# CE842170260_SHEET4.net
KiCad netlist of a schematic drawn in Altium Designer
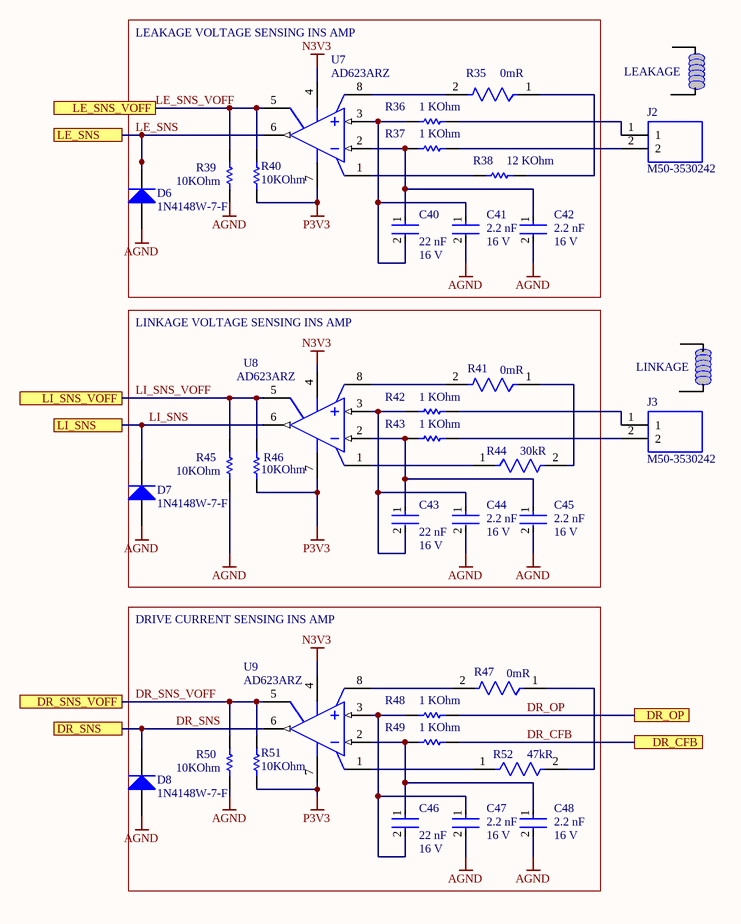
[diagram p0: CE842170260_SHEET4.SchDoc]

(export (version "E")
  (design (tool "Eeschema 10.0.6"))
  (components
    (comp (ref "C40")
      (value "CC0402KRX7R7BB223")
      (footprint "FP-CC0402-MFG")
      (description "CAP CER 0.022UF 16V X7R 0402")
      (fields
        (field (name "VOLTAGE RATING") "16 V")
        (field (name "OCTOPART") "https://octopart.com/cc0402krx7r7bb223-yageo-42244626")
        (field (name "CAPACITANCE") "22 nF")
        (field (name "TOLERANCE") "0.1")
      )
      (libsource (lib "Altium Content Vault") (part "11868f565c42a9108669ba33697ecf6"))
    )
    (comp (ref "C41")
      (value "CC0402KRX7R7BB222")
      (footprint "FP-CC0402-MFG")
      (description "CAP CER 2200PF 16V X7R 0402")
      (fields
        (field (name "OCTOPART") "https://octopart.com/cc0402krx7r7bb222-yageo-12817657")
        (field (name "MANUFACTURER") "YAGEO")
        (field (name "CAPACITANCE") "2.2 nF")
        (field (name "VOLTAGE RATING") "16 V")
      )
      (libsource (lib "Altium Content Vault") (part "11868f565c42a9108669ba33697ecf6"))
    )
    (comp (ref "C42")
      (value "CC0402KRX7R7BB222")
      (footprint "FP-CC0402-MFG")
      (description "CAP CER 2200PF 16V X7R 0402")
      (fields
        (field (name "OCTOPART") "https://octopart.com/cc0402krx7r7bb222-yageo-12817657")
        (field (name "MANUFACTURER") "YAGEO")
        (field (name "CAPACITANCE") "2.2 nF")
        (field (name "VOLTAGE RATING") "16 V")
      )
      (libsource (lib "Altium Content Vault") (part "11868f565c42a9108669ba33697ecf6"))
    )
    (comp (ref "C43")
      (value "CC0402KRX7R7BB223")
      (footprint "FP-CC0402-MFG")
      (description "CAP CER 0.022UF 16V X7R 0402")
      (fields
        (field (name "VOLTAGE RATING") "16 V")
        (field (name "OCTOPART") "https://octopart.com/cc0402krx7r7bb223-yageo-42244626")
        (field (name "CAPACITANCE") "22 nF")
        (field (name "TOLERANCE") "0.1")
      )
      (libsource (lib "Altium Content Vault") (part "11868f565c42a9108669ba33697ecf6"))
    )
    (comp (ref "C44")
      (value "CC0402KRX7R7BB222")
      (footprint "FP-CC0402-MFG")
      (description "CAP CER 2200PF 16V X7R 0402")
      (fields
        (field (name "OCTOPART") "https://octopart.com/cc0402krx7r7bb222-yageo-12817657")
        (field (name "MANUFACTURER") "YAGEO")
        (field (name "CAPACITANCE") "2.2 nF")
        (field (name "VOLTAGE RATING") "16 V")
      )
      (libsource (lib "Altium Content Vault") (part "11868f565c42a9108669ba33697ecf6"))
    )
    (comp (ref "C45")
      (value "CC0402KRX7R7BB222")
      (footprint "FP-CC0402-MFG")
      (description "CAP CER 2200PF 16V X7R 0402")
      (fields
        (field (name "OCTOPART") "https://octopart.com/cc0402krx7r7bb222-yageo-12817657")
        (field (name "MANUFACTURER") "YAGEO")
        (field (name "CAPACITANCE") "2.2 nF")
        (field (name "VOLTAGE RATING") "16 V")
      )
      (libsource (lib "Altium Content Vault") (part "11868f565c42a9108669ba33697ecf6"))
    )
    (comp (ref "C46")
      (value "CC0402KRX7R7BB223")
      (footprint "FP-CC0402-MFG")
      (description "CAP CER 0.022UF 16V X7R 0402")
      (fields
        (field (name "VOLTAGE RATING") "16 V")
        (field (name "OCTOPART") "https://octopart.com/cc0402krx7r7bb223-yageo-42244626")
        (field (name "CAPACITANCE") "22 nF")
        (field (name "TOLERANCE") "0.1")
      )
      (libsource (lib "Altium Content Vault") (part "11868f565c42a9108669ba33697ecf6"))
    )
    (comp (ref "C47")
      (value "CC0402KRX7R7BB222")
      (footprint "FP-CC0402-MFG")
      (description "CAP CER 2200PF 16V X7R 0402")
      (fields
        (field (name "OCTOPART") "https://octopart.com/cc0402krx7r7bb222-yageo-12817657")
        (field (name "MANUFACTURER") "YAGEO")
        (field (name "CAPACITANCE") "2.2 nF")
        (field (name "VOLTAGE RATING") "16 V")
      )
      (libsource (lib "Altium Content Vault") (part "11868f565c42a9108669ba33697ecf6"))
    )
    (comp (ref "C48")
      (value "CC0402KRX7R7BB222")
      (footprint "FP-CC0402-MFG")
      (description "CAP CER 2200PF 16V X7R 0402")
      (fields
        (field (name "OCTOPART") "https://octopart.com/cc0402krx7r7bb222-yageo-12817657")
        (field (name "MANUFACTURER") "YAGEO")
        (field (name "CAPACITANCE") "2.2 nF")
        (field (name "VOLTAGE RATING") "16 V")
      )
      (libsource (lib "Altium Content Vault") (part "11868f565c42a9108669ba33697ecf6"))
    )
    (comp (ref "D6")
      (value "1N4148W-7-F")
      (footprint "DIOD-SOD123-2_V")
      (description "Fast Switching Diode, 100 V, 0.15 A, -65 to 150 degC, 2-Pin?SOD123, RoHS, Tape and Reel")
      (fields (field (name "MANUFACTURER") "DiodesIncorporated"))
      (libsource (lib "Altium Content Vault") (part "D-AK-2"))
    )
    (comp (ref "D7")
      (value "1N4148W-7-F")
      (footprint "DIOD-SOD123-2_V")
      (description "Fast Switching Diode, 100 V, 0.15 A, -65 to 150 degC, 2-Pin?SOD123, RoHS, Tape and Reel")
      (fields (field (name "MANUFACTURER") "DiodesIncorporated"))
      (libsource (lib "Altium Content Vault") (part "D-AK-2"))
    )
    (comp (ref "D8")
      (value "1N4148W-7-F")
      (footprint "DIOD-SOD123-2_V")
      (description "Fast Switching Diode, 100 V, 0.15 A, -65 to 150 degC, 2-Pin?SOD123, RoHS, Tape and Reel")
      (fields (field (name "MANUFACTURER") "DiodesIncorporated"))
      (libsource (lib "Altium Content Vault") (part "D-AK-2"))
    )
    (comp (ref "J2")
      (value "M50-3530242")
      (footprint "HDRV2W40P0X127_1X2_254X210X420P")
      (description "Headers & Wire Housings 2 WAY SIL VERT PC TAIL P/HDR")
      (fields (field (name "MOUSER PART NUMBER") "855-M50-3530242"))
      (libsource (lib "M50-3530242") (part "M50-3530242"))
    )
    (comp (ref "J3")
      (value "M50-3530242")
      (footprint "HDRV2W40P0X127_1X2_254X210X420P")
      (description "Headers & Wire Housings 2 WAY SIL VERT PC TAIL P/HDR")
      (fields (field (name "MOUSER PART NUMBER") "855-M50-3530242"))
      (libsource (lib "M50-3530242") (part "M50-3530242"))
    )
    (comp (ref "R35")
      (value "MCS04020Z0000ZE000")
      (footprint "FP-MCS0402-MFG")
      (description "RES SMD 1.2K OHM 1% 1/10W 0402")
      (fields (field (name "RESISTANCE") "0mR"))
      (libsource (lib "Altium Content Vault") (part "1029c3af85768c4190bb7ad29bc67b5"))
    )
    (comp (ref "R36")
      (value "ERJ-2RKF1001X")
      (footprint "RESC1005X40X25NL05T05")
      (description "Chip Resistor, 1 KOhm, +/- 1%, 100 mW, -55 to 155 degC, 0402 (1005 Metric), RoHS, Tape and Reel")
      (fields
        (field (name "MANUFACTURER") "Basic Passives")
        (field (name "TOLERANCE") "1%")
        (field (name "RESISTANCE") "1 KOhm")
      )
      (libsource (lib "Altium Content Vault") (part "RES-2"))
    )
    (comp (ref "R37")
      (value "ERJ-2RKF1001X")
      (footprint "RESC1005X40X25NL05T05")
      (description "Chip Resistor, 1 KOhm, +/- 1%, 100 mW, -55 to 155 degC, 0402 (1005 Metric), RoHS, Tape and Reel")
      (fields
        (field (name "MANUFACTURER") "Basic Passives")
        (field (name "TOLERANCE") "1%")
        (field (name "RESISTANCE") "1 KOhm")
      )
      (libsource (lib "Altium Content Vault") (part "RES-2"))
    )
    (comp (ref "R38")
      (value "ERJ-2RKF1202X")
      (footprint "RESC1005X40X25ML05T05")
      (description "Chip Resistor, 12 KOhm, +/- 1%, 0.1 W, -55 to 155 degC, 0402 (1005 Metric), RoHS, Tape and Reel")
      (fields (field (name "RESISTANCE") "12 KOhm") (field (name "TOLERANCE") "1%"))
      (libsource (lib "Altium Content Vault") (part "RES-2"))
    )
    (comp (ref "R39")
      (value "ERJ2RKF1002X")
      (footprint "RESC1005X40X25LL05T05")
      (description "Chip Resistor, 10 KOhm, +/- 1%, 0.1 W, -55 to 155 degC, 0402 (1005 Metric), RoHS, Tape and Reel")
      (fields
        (field (name "RESISTANCE") "10KOhm")
        (field (name "TOLERANCE") "1%")
        (field (name "MANUFACTURER") "Panasonic")
      )
      (libsource (lib "Altium Content Vault") (part "RES-2"))
    )
    (comp (ref "R40")
      (value "ERJ2RKF1002X")
      (footprint "RESC1005X40X25LL05T05")
      (description "Chip Resistor, 10 KOhm, +/- 1%, 0.1 W, -55 to 155 degC, 0402 (1005 Metric), RoHS, Tape and Reel")
      (fields
        (field (name "RESISTANCE") "10KOhm")
        (field (name "TOLERANCE") "1%")
        (field (name "MANUFACTURER") "Panasonic")
      )
      (libsource (lib "Altium Content Vault") (part "RES-2"))
    )
    (comp (ref "R41")
      (value "MCS04020Z0000ZE000")
      (footprint "FP-MCS0402-MFG")
      (description "RES SMD 1.2K OHM 1% 1/10W 0402")
      (fields (field (name "RESISTANCE") "0mR"))
      (libsource (lib "Altium Content Vault") (part "1029c3af85768c4190bb7ad29bc67b5"))
    )
    (comp (ref "R42")
      (value "ERJ-2RKF1001X")
      (footprint "RESC1005X40X25NL05T05")
      (description "Chip Resistor, 1 KOhm, +/- 1%, 100 mW, -55 to 155 degC, 0402 (1005 Metric), RoHS, Tape and Reel")
      (fields
        (field (name "MANUFACTURER") "Basic Passives")
        (field (name "TOLERANCE") "1%")
        (field (name "RESISTANCE") "1 KOhm")
      )
      (libsource (lib "Altium Content Vault") (part "RES-2"))
    )
    (comp (ref "R43")
      (value "ERJ-2RKF1001X")
      (footprint "RESC1005X40X25NL05T05")
      (description "Chip Resistor, 1 KOhm, +/- 1%, 100 mW, -55 to 155 degC, 0402 (1005 Metric), RoHS, Tape and Reel")
      (fields
        (field (name "MANUFACTURER") "Basic Passives")
        (field (name "TOLERANCE") "1%")
        (field (name "RESISTANCE") "1 KOhm")
      )
      (libsource (lib "Altium Content Vault") (part "RES-2"))
    )
    (comp (ref "R44")
      (value "ERJ-2RKF3002X")
      (footprint "FP-ERJ2RK-IPC_C")
      (description "RES SMD 30K OHM 1% 1/10W 0402")
      (fields (field (name "RESISTANCE") "30kR") (field (name "TOLERANCE") "1%"))
      (libsource (lib "Altium Content Vault") (part "1029c3af85768c4190bb7ad29bc67b5"))
    )
    (comp (ref "R45")
      (value "ERJ2RKF1002X")
      (footprint "RESC1005X40X25LL05T05")
      (description "Chip Resistor, 10 KOhm, +/- 1%, 0.1 W, -55 to 155 degC, 0402 (1005 Metric), RoHS, Tape and Reel")
      (fields
        (field (name "RESISTANCE") "10KOhm")
        (field (name "TOLERANCE") "1%")
        (field (name "MANUFACTURER") "Panasonic")
      )
      (libsource (lib "Altium Content Vault") (part "RES-2"))
    )
    (comp (ref "R46")
      (value "ERJ2RKF1002X")
      (footprint "RESC1005X40X25LL05T05")
      (description "Chip Resistor, 10 KOhm, +/- 1%, 0.1 W, -55 to 155 degC, 0402 (1005 Metric), RoHS, Tape and Reel")
      (fields
        (field (name "RESISTANCE") "10KOhm")
        (field (name "TOLERANCE") "1%")
        (field (name "MANUFACTURER") "Panasonic")
      )
      (libsource (lib "Altium Content Vault") (part "RES-2"))
    )
    (comp (ref "R47")
      (value "MCS04020Z0000ZE000")
      (footprint "FP-MCS0402-MFG")
      (description "RES SMD 1.2K OHM 1% 1/10W 0402")
      (fields (field (name "RESISTANCE") "0mR"))
      (libsource (lib "Altium Content Vault") (part "1029c3af85768c4190bb7ad29bc67b5"))
    )
    (comp (ref "R48")
      (value "ERJ-2RKF1001X")
      (footprint "RESC1005X40X25NL05T05")
      (description "Chip Resistor, 1 KOhm, +/- 1%, 100 mW, -55 to 155 degC, 0402 (1005 Metric), RoHS, Tape and Reel")
      (fields
        (field (name "MANUFACTURER") "Basic Passives")
        (field (name "TOLERANCE") "1%")
        (field (name "RESISTANCE") "1 KOhm")
      )
      (libsource (lib "Altium Content Vault") (part "RES-2"))
    )
    (comp (ref "R49")
      (value "ERJ-2RKF1001X")
      (footprint "RESC1005X40X25NL05T05")
      (description "Chip Resistor, 1 KOhm, +/- 1%, 100 mW, -55 to 155 degC, 0402 (1005 Metric), RoHS, Tape and Reel")
      (fields
        (field (name "MANUFACTURER") "Basic Passives")
        (field (name "TOLERANCE") "1%")
        (field (name "RESISTANCE") "1 KOhm")
      )
      (libsource (lib "Altium Content Vault") (part "RES-2"))
    )
    (comp (ref "R50")
      (value "ERJ2RKF1002X")
      (footprint "RESC1005X40X25LL05T05")
      (description "Chip Resistor, 10 KOhm, +/- 1%, 0.1 W, -55 to 155 degC, 0402 (1005 Metric), RoHS, Tape and Reel")
      (fields
        (field (name "RESISTANCE") "10KOhm")
        (field (name "TOLERANCE") "1%")
        (field (name "MANUFACTURER") "Panasonic")
      )
      (libsource (lib "Altium Content Vault") (part "RES-2"))
    )
    (comp (ref "R51")
      (value "ERJ2RKF1002X")
      (footprint "RESC1005X40X25LL05T05")
      (description "Chip Resistor, 10 KOhm, +/- 1%, 0.1 W, -55 to 155 degC, 0402 (1005 Metric), RoHS, Tape and Reel")
      (fields
        (field (name "RESISTANCE") "10KOhm")
        (field (name "TOLERANCE") "1%")
        (field (name "MANUFACTURER") "Panasonic")
      )
      (libsource (lib "Altium Content Vault") (part "RES-2"))
    )
    (comp (ref "R52")
      (value "ERJ-2RKF4702X")
      (footprint "FP-ERJ2RK-IPC_B")
      (description "RES SMD 47K OHM 1% 1/10W 0402")
      (fields (field (name "RESISTANCE") "47kR") (field (name "TOLERANCE") "1%"))
      (libsource (lib "Altium Content Vault") (part "1029c3af85768c4190bb7ad29bc67b5"))
    )
    (comp (ref "U7")
      (value "AD623ARZ")
      (footprint "ADI-AD623ARZ-8_M")
      (fields (field (name "MANUFACTURER") "Analog Devices"))
      (libsource (lib "Altium Content Vault") (part "ADI-AD623ARZ-8"))
    )
    (comp (ref "U8")
      (value "AD623ARZ")
      (footprint "ADI-AD623ARZ-8_M")
      (fields (field (name "MANUFACTURER") "Analog Devices"))
      (libsource (lib "Altium Content Vault") (part "ADI-AD623ARZ-8"))
    )
    (comp (ref "U9")
      (value "AD623ARZ")
      (footprint "ADI-AD623ARZ-8_M")
      (fields (field (name "MANUFACTURER") "Analog Devices"))
      (libsource (lib "Altium Content Vault") (part "ADI-AD623ARZ-8"))
    )
  )
  (nets
    (net (code "1") (name "/DR_CFB") (class "Default")
      (node (ref "R49") (pin "1") (pinfunction "1_1") (pintype "passive"))
    )
    (net (code "2") (name "/DR_OP") (class "Default")
      (node (ref "R48") (pin "1") (pinfunction "1_1") (pintype "passive"))
    )
    (net (code "3") (name "/DR_SNS") (class "Default")
      (node (ref "D8") (pin "2") (pinfunction "K_2") (pintype "passive"))
      (node (ref "U9") (pin "6") (pinfunction "OUTPUT_6") (pintype "output"))
    )
    (net (code "4") (name "/DR_SNS_VOFF") (class "Default")
      (node (ref "R50") (pin "2") (pinfunction "2_2") (pintype "passive"))
      (node (ref "R51") (pin "1") (pinfunction "1_1") (pintype "passive"))
      (node (ref "U9") (pin "5") (pinfunction "REF_5") (pintype "power_in"))
    )
    (net (code "5") (name "/LE_SNS") (class "Default")
      (node (ref "D6") (pin "2") (pinfunction "K_2") (pintype "passive"))
      (node (ref "U7") (pin "6") (pinfunction "OUTPUT_6") (pintype "output"))
    )
    (net (code "6") (name "/LE_SNS_VOFF") (class "Default")
      (node (ref "R39") (pin "2") (pinfunction "2_2") (pintype "passive"))
      (node (ref "R40") (pin "1") (pinfunction "1_1") (pintype "passive"))
      (node (ref "U7") (pin "5") (pinfunction "REF_5") (pintype "power_in"))
    )
    (net (code "7") (name "/LI_SNS") (class "Default")
      (node (ref "D7") (pin "2") (pinfunction "K_2") (pintype "passive"))
      (node (ref "U8") (pin "6") (pinfunction "OUTPUT_6") (pintype "output"))
    )
    (net (code "8") (name "/LI_SNS_VOFF") (class "Default")
      (node (ref "R45") (pin "2") (pinfunction "2_2") (pintype "passive"))
      (node (ref "R46") (pin "1") (pinfunction "1_1") (pintype "passive"))
      (node (ref "U8") (pin "5") (pinfunction "REF_5") (pintype "power_in"))
    )
    (net (code "9") (name "AGND") (class "Default")
      (node (ref "C41") (pin "2") (pinfunction "2_2") (pintype "passive"))
      (node (ref "C42") (pin "2") (pinfunction "2_2") (pintype "passive"))
      (node (ref "C44") (pin "2") (pinfunction "2_2") (pintype "passive"))
      (node (ref "C45") (pin "2") (pinfunction "2_2") (pintype "passive"))
      (node (ref "C47") (pin "2") (pinfunction "2_2") (pintype "passive"))
      (node (ref "C48") (pin "2") (pinfunction "2_2") (pintype "passive"))
      (node (ref "D6") (pin "1") (pinfunction "A_1") (pintype "passive"))
      (node (ref "D7") (pin "1") (pinfunction "A_1") (pintype "passive"))
      (node (ref "D8") (pin "1") (pinfunction "A_1") (pintype "passive"))
      (node (ref "R39") (pin "1") (pinfunction "1_1") (pintype "passive"))
      (node (ref "R45") (pin "1") (pinfunction "1_1") (pintype "passive"))
      (node (ref "R50") (pin "1") (pinfunction "1_1") (pintype "passive"))
    )
    (net (code "10") (name "N3V3") (class "Default")
      (node (ref "U7") (pin "4") (pinfunction "-VS_4") (pintype "power_in"))
      (node (ref "U8") (pin "4") (pinfunction "-VS_4") (pintype "power_in"))
      (node (ref "U9") (pin "4") (pinfunction "-VS_4") (pintype "power_in"))
    )
    (net (code "11") (name "Net-(J2-Pad1)") (class "Default")
      (node (ref "J2") (pin "1") (pinfunction "1_1") (pintype "passive"))
      (node (ref "R36") (pin "1") (pinfunction "1_1") (pintype "passive"))
    )
    (net (code "12") (name "Net-(J2-Pad2)") (class "Default")
      (node (ref "J2") (pin "2") (pinfunction "2_2") (pintype "passive"))
      (node (ref "R37") (pin "1") (pinfunction "1_1") (pintype "passive"))
    )
    (net (code "13") (name "Net-(J3-Pad1)") (class "Default")
      (node (ref "J3") (pin "1") (pinfunction "1_1") (pintype "passive"))
      (node (ref "R42") (pin "1") (pinfunction "1_1") (pintype "passive"))
    )
    (net (code "14") (name "Net-(J3-Pad2)") (class "Default")
      (node (ref "J3") (pin "2") (pinfunction "2_2") (pintype "passive"))
      (node (ref "R43") (pin "1") (pinfunction "1_1") (pintype "passive"))
    )
    (net (code "15") (name "Net-(R35-Pad1)") (class "Default")
      (node (ref "R35") (pin "1") (pinfunction "1_1") (pintype "passive"))
      (node (ref "R38") (pin "2") (pinfunction "2_2") (pintype "passive"))
    )
    (net (code "16") (name "Net-(R41-Pad1)") (class "Default")
      (node (ref "R41") (pin "1") (pinfunction "1_1") (pintype "passive"))
      (node (ref "R44") (pin "2") (pinfunction "2_2") (pintype "passive"))
    )
    (net (code "17") (name "Net-(R47-Pad1)") (class "Default")
      (node (ref "R47") (pin "1") (pinfunction "1_1") (pintype "passive"))
      (node (ref "R52") (pin "2") (pinfunction "2_2") (pintype "passive"))
    )
    (net (code "18") (name "Net-(U7-+IN)") (class "Default")
      (node (ref "C40") (pin "2") (pinfunction "2_2") (pintype "passive"))
      (node (ref "C41") (pin "1") (pinfunction "1_1") (pintype "passive"))
      (node (ref "R36") (pin "2") (pinfunction "2_2") (pintype "passive"))
      (node (ref "U7") (pin "3") (pinfunction "+IN_3") (pintype "input"))
    )
    (net (code "19") (name "Net-(U7-+RG)") (class "Default")
      (node (ref "R35") (pin "2") (pinfunction "2_2") (pintype "passive"))
      (node (ref "U7") (pin "8") (pinfunction "+RG_8") (pintype "passive"))
    )
    (net (code "20") (name "Net-(U7--IN)") (class "Default")
      (node (ref "C40") (pin "1") (pinfunction "1_1") (pintype "passive"))
      (node (ref "C42") (pin "1") (pinfunction "1_1") (pintype "passive"))
      (node (ref "R37") (pin "2") (pinfunction "2_2") (pintype "passive"))
      (node (ref "U7") (pin "2") (pinfunction "-IN_2") (pintype "input"))
    )
    (net (code "21") (name "Net-(U7--RG)") (class "Default")
      (node (ref "R38") (pin "1") (pinfunction "1_1") (pintype "passive"))
      (node (ref "U7") (pin "1") (pinfunction "-RG_1") (pintype "passive"))
    )
    (net (code "22") (name "Net-(U8-+IN)") (class "Default")
      (node (ref "C43") (pin "2") (pinfunction "2_2") (pintype "passive"))
      (node (ref "C44") (pin "1") (pinfunction "1_1") (pintype "passive"))
      (node (ref "R42") (pin "2") (pinfunction "2_2") (pintype "passive"))
      (node (ref "U8") (pin "3") (pinfunction "+IN_3") (pintype "input"))
    )
    (net (code "23") (name "Net-(U8-+RG)") (class "Default")
      (node (ref "R41") (pin "2") (pinfunction "2_2") (pintype "passive"))
      (node (ref "U8") (pin "8") (pinfunction "+RG_8") (pintype "passive"))
    )
    (net (code "24") (name "Net-(U8--IN)") (class "Default")
      (node (ref "C43") (pin "1") (pinfunction "1_1") (pintype "passive"))
      (node (ref "C45") (pin "1") (pinfunction "1_1") (pintype "passive"))
      (node (ref "R43") (pin "2") (pinfunction "2_2") (pintype "passive"))
      (node (ref "U8") (pin "2") (pinfunction "-IN_2") (pintype "input"))
    )
    (net (code "25") (name "Net-(U8--RG)") (class "Default")
      (node (ref "R44") (pin "1") (pinfunction "1_1") (pintype "passive"))
      (node (ref "U8") (pin "1") (pinfunction "-RG_1") (pintype "passive"))
    )
    (net (code "26") (name "Net-(U9-+IN)") (class "Default")
      (node (ref "C46") (pin "2") (pinfunction "2_2") (pintype "passive"))
      (node (ref "C47") (pin "1") (pinfunction "1_1") (pintype "passive"))
      (node (ref "R48") (pin "2") (pinfunction "2_2") (pintype "passive"))
      (node (ref "U9") (pin "3") (pinfunction "+IN_3") (pintype "input"))
    )
    (net (code "27") (name "Net-(U9-+RG)") (class "Default")
      (node (ref "R47") (pin "2") (pinfunction "2_2") (pintype "passive"))
      (node (ref "U9") (pin "8") (pinfunction "+RG_8") (pintype "passive"))
    )
    (net (code "28") (name "Net-(U9--IN)") (class "Default")
      (node (ref "C46") (pin "1") (pinfunction "1_1") (pintype "passive"))
      (node (ref "C48") (pin "1") (pinfunction "1_1") (pintype "passive"))
      (node (ref "R49") (pin "2") (pinfunction "2_2") (pintype "passive"))
      (node (ref "U9") (pin "2") (pinfunction "-IN_2") (pintype "input"))
    )
    (net (code "29") (name "Net-(U9--RG)") (class "Default")
      (node (ref "R52") (pin "1") (pinfunction "1_1") (pintype "passive"))
      (node (ref "U9") (pin "1") (pinfunction "-RG_1") (pintype "passive"))
    )
    (net (code "30") (name "P3V3") (class "Default")
      (node (ref "R40") (pin "2") (pinfunction "2_2") (pintype "passive"))
      (node (ref "R46") (pin "2") (pinfunction "2_2") (pintype "passive"))
      (node (ref "R51") (pin "2") (pinfunction "2_2") (pintype "passive"))
      (node (ref "U7") (pin "7") (pinfunction "+VS_7") (pintype "power_in"))
      (node (ref "U8") (pin "7") (pinfunction "+VS_7") (pintype "power_in"))
      (node (ref "U9") (pin "7") (pinfunction "+VS_7") (pintype "power_in"))
    )
  )
)
